# MYO_ESPControlBoard_Rev_1.net
KiCad netlist of a schematic drawn in EAGLE
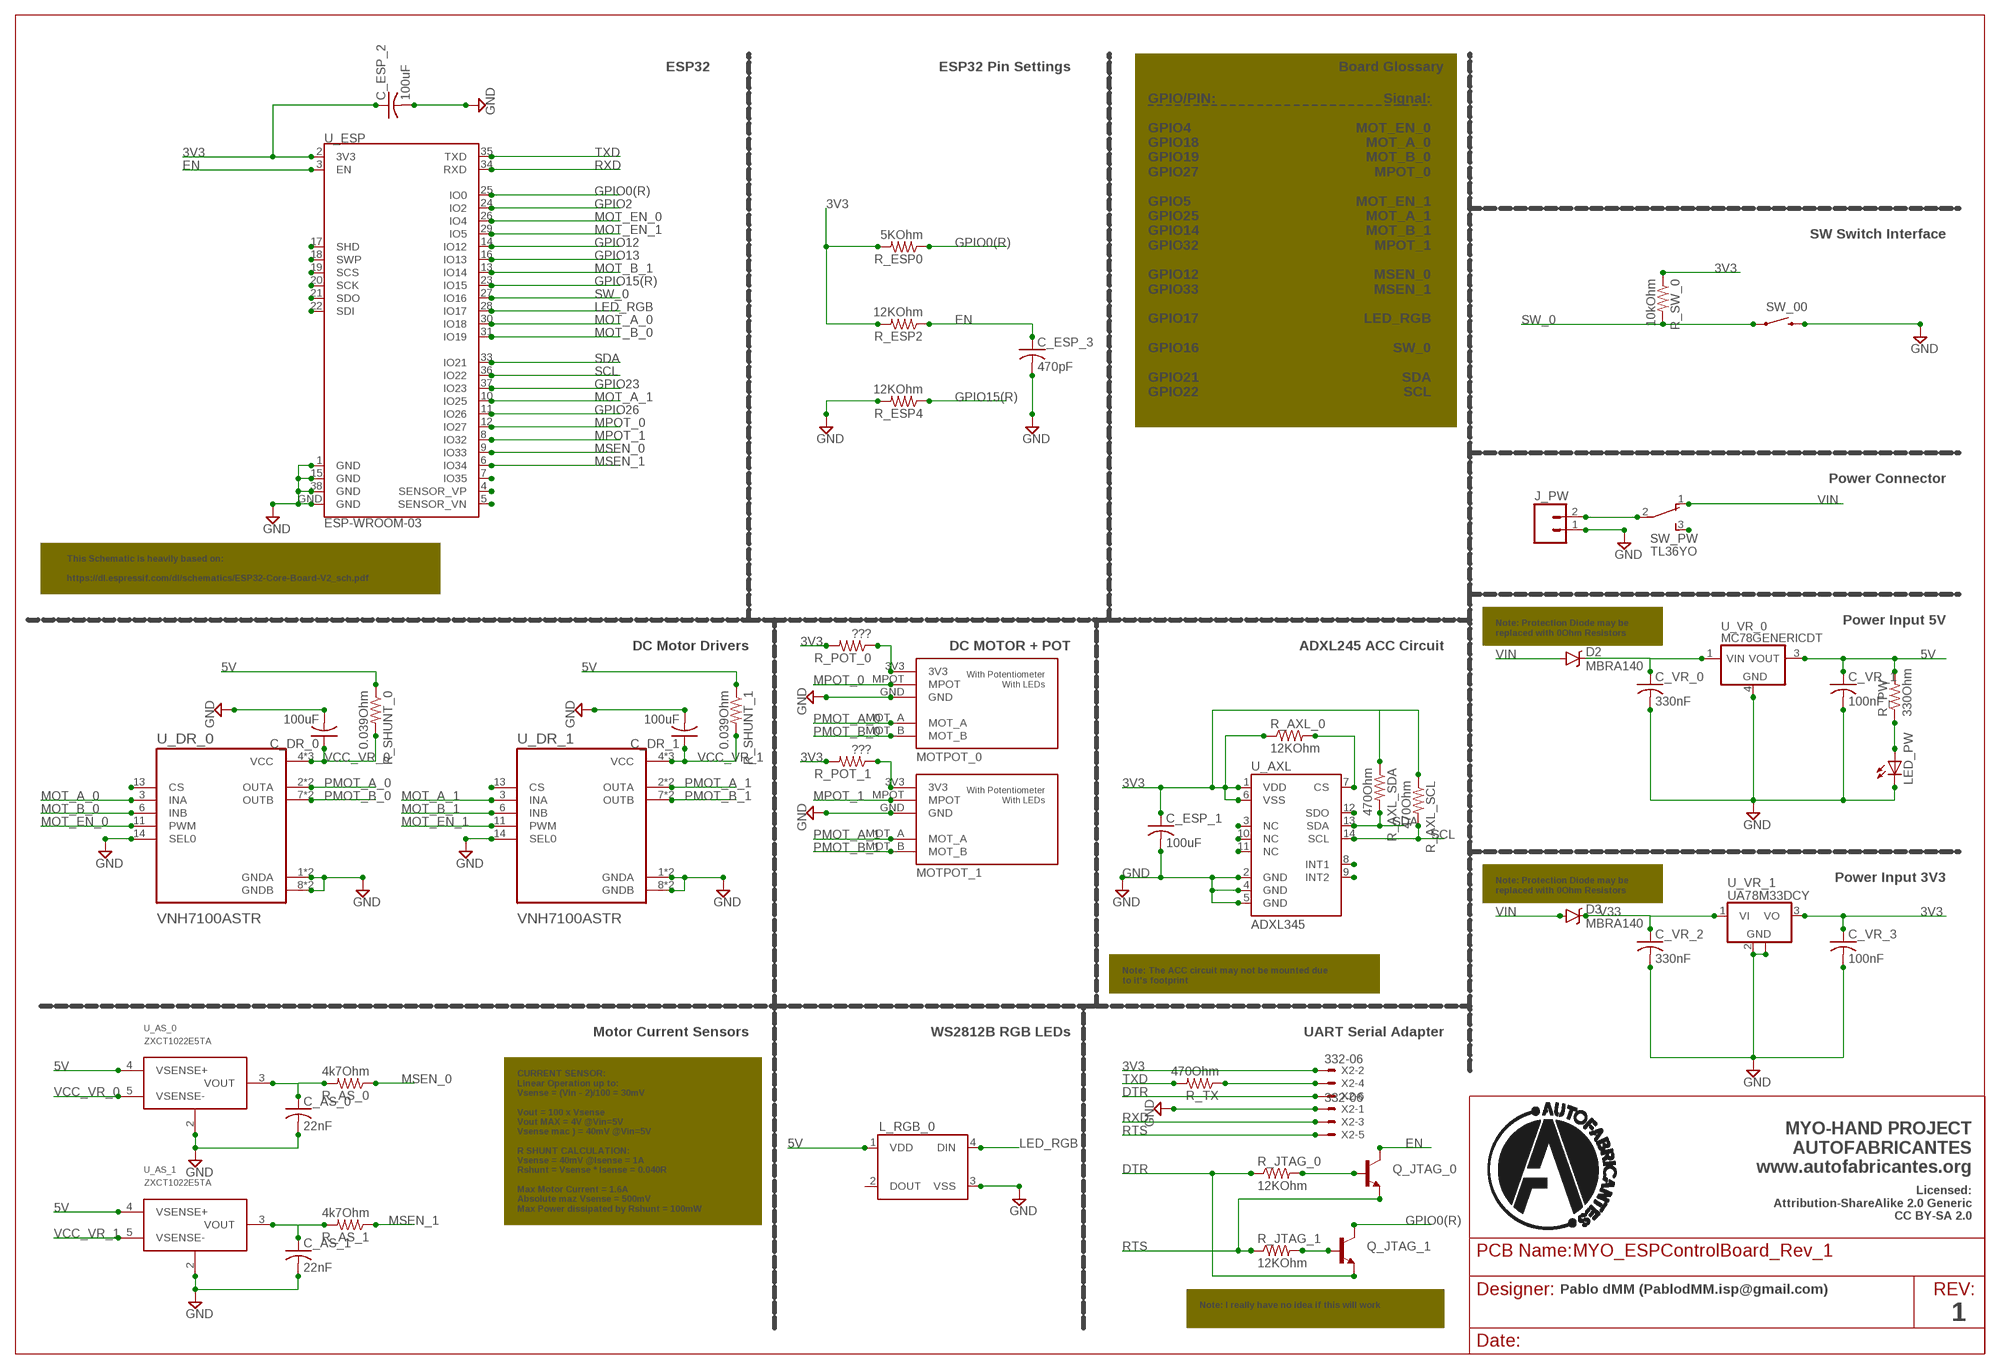
[diagram p0: schematic, sheet 1]

(export (version "E")
  (design (tool "Eeschema 10.0.6"))
  (components
    (comp (ref "C_AS_0")
      (value "22nF")
      (footprint "eagle-import:C0805K")
      (libsource (lib "eagle-import") (part "C-USC0805K"))
    )
    (comp (ref "C_AS_1")
      (value "22nF")
      (footprint "eagle-import:C0805K")
      (libsource (lib "eagle-import") (part "C-USC0805K"))
    )
    (comp (ref "C_DR_0")
      (value "100uF")
      (footprint "eagle-import:C0805K")
      (libsource (lib "eagle-import") (part "C-USC0805K"))
    )
    (comp (ref "C_DR_1")
      (value "100uF")
      (footprint "eagle-import:C0805K")
      (libsource (lib "eagle-import") (part "C-USC0805K"))
    )
    (comp (ref "C_ESP_1")
      (value "100uF")
      (footprint "eagle-import:C0805K")
      (libsource (lib "eagle-import") (part "C-USC0805K"))
    )
    (comp (ref "C_ESP_2")
      (value "100uF")
      (footprint "eagle-import:C0805K")
      (libsource (lib "eagle-import") (part "C-USC0805K"))
    )
    (comp (ref "C_ESP_3")
      (value "470pF")
      (footprint "eagle-import:C0805K")
      (libsource (lib "eagle-import") (part "C-USC0805K"))
    )
    (comp (ref "C_VR_0")
      (value "330nF")
      (footprint "eagle-import:C0805")
      (libsource (lib "eagle-import") (part "C-USC0805"))
    )
    (comp (ref "C_VR_1")
      (value "100nF")
      (footprint "eagle-import:C0805")
      (libsource (lib "eagle-import") (part "C-USC0805"))
    )
    (comp (ref "C_VR_2")
      (value "330nF")
      (footprint "eagle-import:C0805")
      (libsource (lib "eagle-import") (part "C-USC0805"))
    )
    (comp (ref "C_VR_3")
      (value "100nF")
      (footprint "eagle-import:C0805")
      (libsource (lib "eagle-import") (part "C-USC0805"))
    )
    (comp (ref "D2")
      (value "MBRA140")
      (footprint "eagle-import:SMA-DIODE")
      (libsource (lib "eagle-import") (part "MBRA140"))
    )
    (comp (ref "D3")
      (value "MBRA140")
      (footprint "eagle-import:SMA-DIODE")
      (libsource (lib "eagle-import") (part "MBRA140"))
    )
    (comp (ref "J_PW")
      (value "M02-JST-2MM-SMT")
      (footprint "eagle-import:JST-2-SMD")
      (libsource (lib "eagle-import") (part "M02-JST-2MM-SMT"))
    )
    (comp (ref "LED_PW")
      (value "LEDSMT1206")
      (footprint "eagle-import:1206")
      (libsource (lib "eagle-import") (part "LEDSMT1206"))
    )
    (comp (ref "L_RGB_0")
      (value "WS2812B")
      (footprint "eagle-import:WS2812B")
      (libsource (lib "eagle-import") (part "WS2812B"))
    )
    (comp (ref "MOTPOT_0")
      (value "POLOLU_MOT_POT")
      (footprint "eagle-import:POLOLU_MOT_POT")
      (libsource (lib "eagle-import") (part "POLOLU_MOT_POT"))
    )
    (comp (ref "MOTPOT_1")
      (value "POLOLU_MOT_POT")
      (footprint "eagle-import:POLOLU_MOT_POT")
      (libsource (lib "eagle-import") (part "POLOLU_MOT_POT"))
    )
    (comp (ref "Q_JTAG_0")
      (value "TRANSISTOR_NPNSOT23-3")
      (footprint "eagle-import:SOT23-3")
      (libsource (lib "eagle-import") (part "TRANSISTOR_NPNSOT23-3"))
    )
    (comp (ref "Q_JTAG_1")
      (value "TRANSISTOR_NPNSOT23-3")
      (footprint "eagle-import:SOT23-3")
      (libsource (lib "eagle-import") (part "TRANSISTOR_NPNSOT23-3"))
    )
    (comp (ref "R_AS_0")
      (value "4k7Ohm")
      (footprint "eagle-import:M0805")
      (libsource (lib "eagle-import") (part "R-US_M0805"))
    )
    (comp (ref "R_AS_1")
      (value "4k7Ohm")
      (footprint "eagle-import:M0805")
      (libsource (lib "eagle-import") (part "R-US_M0805"))
    )
    (comp (ref "R_AXL_0")
      (value "12KOhm")
      (footprint "eagle-import:M0805")
      (libsource (lib "eagle-import") (part "R-US_M0805"))
    )
    (comp (ref "R_AXL_SCL")
      (value "470Ohm")
      (footprint "eagle-import:M0805")
      (libsource (lib "eagle-import") (part "R-US_M0805"))
    )
    (comp (ref "R_AXL_SDA")
      (value "470Ohm")
      (footprint "eagle-import:M0805")
      (libsource (lib "eagle-import") (part "R-US_M0805"))
    )
    (comp (ref "R_ESP0")
      (value "5KOhm")
      (footprint "eagle-import:M0805")
      (libsource (lib "eagle-import") (part "R-US_M0805"))
    )
    (comp (ref "R_ESP2")
      (value "12KOhm")
      (footprint "eagle-import:M0805")
      (libsource (lib "eagle-import") (part "R-US_M0805"))
    )
    (comp (ref "R_ESP4")
      (value "12KOhm")
      (footprint "eagle-import:M0805")
      (libsource (lib "eagle-import") (part "R-US_M0805"))
    )
    (comp (ref "R_JTAG_0")
      (value "12KOhm")
      (footprint "eagle-import:M0805")
      (libsource (lib "eagle-import") (part "R-US_M0805"))
    )
    (comp (ref "R_JTAG_1")
      (value "12KOhm")
      (footprint "eagle-import:M0805")
      (libsource (lib "eagle-import") (part "R-US_M0805"))
    )
    (comp (ref "R_POT_0")
      (value "???")
      (footprint "eagle-import:M0805")
      (libsource (lib "eagle-import") (part "R-US_M0805"))
    )
    (comp (ref "R_POT_1")
      (value "???")
      (footprint "eagle-import:M0805")
      (libsource (lib "eagle-import") (part "R-US_M0805"))
    )
    (comp (ref "R_PW")
      (value "330Ohm")
      (footprint "eagle-import:M0805")
      (libsource (lib "eagle-import") (part "R-US_M0805"))
    )
    (comp (ref "R_SHUNT_0")
      (value "0.039Ohm")
      (footprint "eagle-import:M0805")
      (libsource (lib "eagle-import") (part "R-US_M0805"))
    )
    (comp (ref "R_SHUNT_1")
      (value "0.039Ohm")
      (footprint "eagle-import:M0805")
      (libsource (lib "eagle-import") (part "R-US_M0805"))
    )
    (comp (ref "R_SW_0")
      (value "10kOhm")
      (footprint "eagle-import:M0805")
      (libsource (lib "eagle-import") (part "R-US_M0805"))
    )
    (comp (ref "R_TX")
      (value "470Ohm")
      (footprint "eagle-import:M0805")
      (libsource (lib "eagle-import") (part "R-US_M0805"))
    )
    (comp (ref "SW_00")
      (value "SWITCH-MOMENTARY-2TACTILE-SWITCH-SMD-RIGHT-ANGLE")
      (footprint "eagle-import:TACTILE_SWITCH-SMD-RIGHT-ANGLE")
      (libsource (lib "eagle-import") (part "SWITCH-MOMENTARY-2TACTILE-SWITCH-SMD-RIGHT-ANGLE"))
    )
    (comp (ref "SW_PW")
      (value "TL36YO")
      (footprint "eagle-import:TL3XYO")
      (libsource (lib "eagle-import") (part "TL36YO"))
    )
    (comp (ref "U_AS_0")
      (value "ZXCT1022E5TA")
      (footprint "eagle-import:SOT95P270X145-5N(SOT23-5)")
      (fields (field (name "DIGI-KEY_PART_NUMBER") "ZXCT1022E5TACT-ND") (field (name "MF") "Diodes Inc."))
      (libsource (lib "eagle-import") (part "ZXCT1022E5TA"))
    )
    (comp (ref "U_AS_1")
      (value "ZXCT1022E5TA")
      (footprint "eagle-import:SOT95P270X145-5N(SOT23-5)")
      (fields (field (name "DIGI-KEY_PART_NUMBER") "ZXCT1022E5TACT-ND") (field (name "MF") "Diodes Inc."))
      (libsource (lib "eagle-import") (part "ZXCT1022E5TA"))
    )
    (comp (ref "U_AXL")
      (value "ADXL345")
      (footprint "eagle-import:LGA14")
      (libsource (lib "eagle-import") (part "ADXL345"))
    )
    (comp (ref "U_DR_0")
      (value "VNH7100ASTR")
      (footprint "eagle-import:SOIC127P600X175-16N")
      (fields (field (name "MF") "STMicroelectronics"))
      (libsource (lib "eagle-import") (part "VNH7100ASTR"))
    )
    (comp (ref "U_DR_1")
      (value "VNH7100ASTR")
      (footprint "eagle-import:SOIC127P600X175-16N")
      (fields (field (name "MF") "STMicroelectronics"))
      (libsource (lib "eagle-import") (part "VNH7100ASTR"))
    )
    (comp (ref "U_ESP")
      (value "ESP-WROOM-03")
      (footprint "eagle-import:ESP-WROOM-03")
      (libsource (lib "eagle-import") (part "ESP-WROOM-03"))
    )
    (comp (ref "U_VR_0")
      (value "MC78GENERICDT")
      (footprint "eagle-import:DPAK-3")
      (libsource (lib "eagle-import") (part "MC78DTGENERIC"))
    )
    (comp (ref "U_VR_1")
      (value "UA78M33DCY")
      (footprint "eagle-import:SOT223")
      (libsource (lib "eagle-import") (part "UA78MDCY33"))
    )
    (comp (ref "X2")
      (value "332-06")
      (footprint "eagle-import:332-06")
      (libsource (lib "eagle-import") (part "332-06"))
    )
  )
  (nets
    (net (code "1") (name "/3V3") (class "Default")
      (node (ref "C_ESP_1") (pin "1") (pinfunction "1_1") (pintype "passive"))
      (node (ref "C_ESP_2") (pin "1") (pinfunction "1_1") (pintype "passive"))
      (node (ref "C_VR_3") (pin "1") (pinfunction "1_1") (pintype "passive"))
      (node (ref "R_AXL_0") (pin "1") (pinfunction "1_1") (pintype "passive"))
      (node (ref "R_AXL_SCL") (pin "1") (pinfunction "1_1") (pintype "passive"))
      (node (ref "R_AXL_SDA") (pin "1") (pinfunction "1_1") (pintype "passive"))
      (node (ref "R_ESP0") (pin "2") (pinfunction "2_2") (pintype "passive"))
      (node (ref "R_ESP2") (pin "2") (pinfunction "2_2") (pintype "passive"))
      (node (ref "R_POT_0") (pin "2") (pinfunction "2_2") (pintype "passive"))
      (node (ref "R_POT_1") (pin "2") (pinfunction "2_2") (pintype "passive"))
      (node (ref "R_SW_0") (pin "1") (pinfunction "1_1") (pintype "passive"))
      (node (ref "U_AXL") (pin "1") (pinfunction "VDD_1") (pintype "bidirectional"))
      (node (ref "U_AXL") (pin "6") (pinfunction "VSS_6") (pintype "bidirectional"))
      (node (ref "U_ESP") (pin "2") (pinfunction "3V3_2") (pintype "bidirectional"))
      (node (ref "U_VR_1") (pin "3") (pinfunction "VO_3") (pintype "passive"))
      (node (ref "X2") (pin "2") (pinfunction "S_2") (pintype "passive"))
    )
    (net (code "2") (name "/5V") (class "Default")
      (node (ref "C_VR_1") (pin "1") (pinfunction "1_1") (pintype "passive"))
      (node (ref "L_RGB_0") (pin "1") (pinfunction "VDD_1") (pintype "power_in"))
      (node (ref "R_PW") (pin "2") (pinfunction "2_2") (pintype "passive"))
      (node (ref "R_SHUNT_0") (pin "1") (pinfunction "1_1") (pintype "passive"))
      (node (ref "R_SHUNT_1") (pin "1") (pinfunction "1_1") (pintype "passive"))
      (node (ref "U_AS_0") (pin "4") (pinfunction "VSENSE+_4") (pintype "input"))
      (node (ref "U_AS_1") (pin "4") (pinfunction "VSENSE+_4") (pintype "input"))
      (node (ref "U_VR_0") (pin "3") (pinfunction "VOUT_3") (pintype "power_in"))
    )
    (net (code "3") (name "/DTR") (class "Default")
      (node (ref "Q_JTAG_1") (pin "2") (pinfunction "E_2") (pintype "passive"))
      (node (ref "R_JTAG_0") (pin "1") (pinfunction "1_1") (pintype "passive"))
      (node (ref "X2") (pin "6") (pinfunction "S_6") (pintype "passive"))
    )
    (net (code "4") (name "/EN") (class "Default")
      (node (ref "C_ESP_3") (pin "1") (pinfunction "1_1") (pintype "passive"))
      (node (ref "Q_JTAG_0") (pin "3") (pinfunction "C_3") (pintype "passive"))
      (node (ref "R_ESP2") (pin "1") (pinfunction "1_1") (pintype "passive"))
      (node (ref "U_ESP") (pin "3") (pinfunction "EN_3") (pintype "bidirectional"))
    )
    (net (code "5") (name "/GPIO0(R)") (class "Default")
      (node (ref "Q_JTAG_1") (pin "3") (pinfunction "C_3") (pintype "passive"))
      (node (ref "R_ESP0") (pin "1") (pinfunction "1_1") (pintype "passive"))
      (node (ref "U_ESP") (pin "25") (pinfunction "IO0_25") (pintype "bidirectional"))
    )
    (net (code "6") (name "/GPIO2") (class "Default")
      (node (ref "U_ESP") (pin "24") (pinfunction "IO2_24") (pintype "bidirectional"))
    )
    (net (code "7") (name "/GPIO12") (class "Default")
      (node (ref "U_ESP") (pin "14") (pinfunction "IO12_14") (pintype "bidirectional"))
    )
    (net (code "8") (name "/GPIO13") (class "Default")
      (node (ref "U_ESP") (pin "16") (pinfunction "IO13_16") (pintype "bidirectional"))
    )
    (net (code "9") (name "/GPIO15(R)") (class "Default")
      (node (ref "R_ESP4") (pin "1") (pinfunction "1_1") (pintype "passive"))
      (node (ref "U_ESP") (pin "23") (pinfunction "IO15_23") (pintype "bidirectional"))
    )
    (net (code "10") (name "/GPIO23") (class "Default")
      (node (ref "U_ESP") (pin "37") (pinfunction "IO23_37") (pintype "bidirectional"))
    )
    (net (code "11") (name "/GPIO26") (class "Default")
      (node (ref "U_ESP") (pin "11") (pinfunction "IO26_11") (pintype "bidirectional"))
    )
    (net (code "12") (name "/LED_RGB") (class "Default")
      (node (ref "L_RGB_0") (pin "4") (pinfunction "DIN_4") (pintype "input"))
      (node (ref "U_ESP") (pin "28") (pinfunction "IO17_28") (pintype "bidirectional"))
    )
    (net (code "13") (name "/MOT_A_0") (class "Default")
      (node (ref "U_DR_0") (pin "3") (pinfunction "INA_3") (pintype "input"))
      (node (ref "U_ESP") (pin "30") (pinfunction "IO18_30") (pintype "bidirectional"))
    )
    (net (code "14") (name "/MOT_A_1") (class "Default")
      (node (ref "U_DR_1") (pin "3") (pinfunction "INA_3") (pintype "input"))
      (node (ref "U_ESP") (pin "10") (pinfunction "IO25_10") (pintype "bidirectional"))
    )
    (net (code "15") (name "/MOT_B_0") (class "Default")
      (node (ref "U_DR_0") (pin "6") (pinfunction "INB_6") (pintype "input"))
      (node (ref "U_ESP") (pin "31") (pinfunction "IO19_31") (pintype "bidirectional"))
    )
    (net (code "16") (name "/MOT_B_1") (class "Default")
      (node (ref "U_DR_1") (pin "6") (pinfunction "INB_6") (pintype "input"))
      (node (ref "U_ESP") (pin "13") (pinfunction "IO14_13") (pintype "bidirectional"))
    )
    (net (code "17") (name "/MOT_EN_0") (class "Default")
      (node (ref "U_DR_0") (pin "11") (pinfunction "PWM_11") (pintype "input"))
      (node (ref "U_ESP") (pin "26") (pinfunction "IO4_26") (pintype "bidirectional"))
    )
    (net (code "18") (name "/MOT_EN_1") (class "Default")
      (node (ref "U_DR_1") (pin "11") (pinfunction "PWM_11") (pintype "input"))
      (node (ref "U_ESP") (pin "29") (pinfunction "IO5_29") (pintype "bidirectional"))
    )
    (net (code "19") (name "/MPOT_0") (class "Default")
      (node (ref "MOTPOT_0") (pin "MPOT") (pinfunction "MPOT_MPOT") (pintype "bidirectional"))
      (node (ref "U_ESP") (pin "12") (pinfunction "IO27_12") (pintype "bidirectional"))
    )
    (net (code "20") (name "/MPOT_1") (class "Default")
      (node (ref "MOTPOT_1") (pin "MPOT") (pinfunction "MPOT_MPOT") (pintype "bidirectional"))
      (node (ref "U_ESP") (pin "8") (pinfunction "IO32_8") (pintype "bidirectional"))
    )
    (net (code "21") (name "/MSEN_0") (class "Default")
      (node (ref "R_AS_0") (pin "1") (pinfunction "1_1") (pintype "passive"))
      (node (ref "U_ESP") (pin "9") (pinfunction "IO33_9") (pintype "bidirectional"))
    )
    (net (code "22") (name "/MSEN_1") (class "Default")
      (node (ref "R_AS_1") (pin "1") (pinfunction "1_1") (pintype "passive"))
      (node (ref "U_ESP") (pin "6") (pinfunction "IO34_6") (pintype "bidirectional"))
    )
    (net (code "23") (name "/PMOT_A_0") (class "Default")
      (node (ref "MOTPOT_0") (pin "MOT_A") (pinfunction "MOT_A_MOT_A") (pintype "bidirectional"))
      (node (ref "U_DR_0") (pin "15") (pinfunction "OUTA_15") (pintype "output"))
      (node (ref "U_DR_0") (pin "2") (pinfunction "OUTA_2") (pintype "output"))
    )
    (net (code "24") (name "/PMOT_A_1") (class "Default")
      (node (ref "MOTPOT_1") (pin "MOT_A") (pinfunction "MOT_A_MOT_A") (pintype "bidirectional"))
      (node (ref "U_DR_1") (pin "15") (pinfunction "OUTA_15") (pintype "output"))
      (node (ref "U_DR_1") (pin "2") (pinfunction "OUTA_2") (pintype "output"))
    )
    (net (code "25") (name "/PMOT_B_0") (class "Default")
      (node (ref "MOTPOT_0") (pin "MOT_B") (pinfunction "MOT_B_MOT_B") (pintype "bidirectional"))
      (node (ref "U_DR_0") (pin "10") (pinfunction "OUTB_10") (pintype "output"))
      (node (ref "U_DR_0") (pin "7") (pinfunction "OUTB_7") (pintype "output"))
    )
    (net (code "26") (name "/PMOT_B_1") (class "Default")
      (node (ref "MOTPOT_1") (pin "MOT_B") (pinfunction "MOT_B_MOT_B") (pintype "bidirectional"))
      (node (ref "U_DR_1") (pin "10") (pinfunction "OUTB_10") (pintype "output"))
      (node (ref "U_DR_1") (pin "7") (pinfunction "OUTB_7") (pintype "output"))
    )
    (net (code "27") (name "/RTS") (class "Default")
      (node (ref "Q_JTAG_0") (pin "2") (pinfunction "E_2") (pintype "passive"))
      (node (ref "R_JTAG_1") (pin "1") (pinfunction "1_1") (pintype "passive"))
      (node (ref "X2") (pin "5") (pinfunction "S_5") (pintype "passive"))
    )
    (net (code "28") (name "/RXD") (class "Default")
      (node (ref "U_ESP") (pin "34") (pinfunction "RXD_34") (pintype "bidirectional"))
      (node (ref "X2") (pin "3") (pinfunction "S_3") (pintype "passive"))
    )
    (net (code "29") (name "/SCL") (class "Default")
      (node (ref "R_AXL_SCL") (pin "2") (pinfunction "2_2") (pintype "passive"))
      (node (ref "U_AXL") (pin "14") (pinfunction "SCL_14") (pintype "bidirectional"))
      (node (ref "U_ESP") (pin "36") (pinfunction "IO22_36") (pintype "bidirectional"))
    )
    (net (code "30") (name "/SDA") (class "Default")
      (node (ref "R_AXL_SDA") (pin "2") (pinfunction "2_2") (pintype "passive"))
      (node (ref "U_AXL") (pin "13") (pinfunction "SDA_13") (pintype "bidirectional"))
      (node (ref "U_ESP") (pin "33") (pinfunction "IO21_33") (pintype "bidirectional"))
    )
    (net (code "31") (name "/SW_0") (class "Default")
      (node (ref "R_SW_0") (pin "2") (pinfunction "2_2") (pintype "passive"))
      (node (ref "SW_00") (pin "1") (pinfunction "1_1") (pintype "passive"))
      (node (ref "U_ESP") (pin "27") (pinfunction "IO16_27") (pintype "bidirectional"))
    )
    (net (code "32") (name "/TXD") (class "Default")
      (node (ref "R_TX") (pin "2") (pinfunction "2_2") (pintype "passive"))
      (node (ref "U_ESP") (pin "35") (pinfunction "TXD_35") (pintype "bidirectional"))
    )
    (net (code "33") (name "/V33") (class "Default")
      (node (ref "C_VR_2") (pin "1") (pinfunction "1_1") (pintype "passive"))
      (node (ref "D3") (pin "C") (pinfunction "C_C") (pintype "passive"))
      (node (ref "U_VR_1") (pin "1") (pinfunction "VI_1") (pintype "input"))
    )
    (net (code "34") (name "/VCC_VR_0") (class "Default")
      (node (ref "C_DR_0") (pin "1") (pinfunction "1_1") (pintype "passive"))
      (node (ref "R_SHUNT_0") (pin "2") (pinfunction "2_2") (pintype "passive"))
      (node (ref "U_AS_0") (pin "5") (pinfunction "VSENSE-_5") (pintype "input"))
      (node (ref "U_DR_0") (pin "12") (pinfunction "VCC_12") (pintype "power_in"))
      (node (ref "U_DR_0") (pin "4") (pinfunction "VCC_4") (pintype "power_in"))
      (node (ref "U_DR_0") (pin "5") (pinfunction "VCC_5") (pintype "power_in"))
    )
    (net (code "35") (name "/VCC_VR_1") (class "Default")
      (node (ref "C_DR_1") (pin "1") (pinfunction "1_1") (pintype "passive"))
      (node (ref "R_SHUNT_1") (pin "2") (pinfunction "2_2") (pintype "passive"))
      (node (ref "U_AS_1") (pin "5") (pinfunction "VSENSE-_5") (pintype "input"))
      (node (ref "U_DR_1") (pin "12") (pinfunction "VCC_12") (pintype "power_in"))
      (node (ref "U_DR_1") (pin "4") (pinfunction "VCC_4") (pintype "power_in"))
      (node (ref "U_DR_1") (pin "5") (pinfunction "VCC_5") (pintype "power_in"))
    )
    (net (code "36") (name "/VIN") (class "Default")
      (node (ref "D2") (pin "A") (pinfunction "A_A") (pintype "passive"))
      (node (ref "D3") (pin "A") (pinfunction "A_A") (pintype "passive"))
      (node (ref "SW_PW") (pin "1") (pinfunction "O_1") (pintype "passive"))
    )
    (net (code "37") (name "GND") (class "Default")
      (node (ref "C_AS_0") (pin "2") (pinfunction "2_2") (pintype "passive"))
      (node (ref "C_AS_1") (pin "2") (pinfunction "2_2") (pintype "passive"))
      (node (ref "C_DR_0") (pin "2") (pinfunction "2_2") (pintype "passive"))
      (node (ref "C_DR_1") (pin "2") (pinfunction "2_2") (pintype "passive"))
      (node (ref "C_ESP_1") (pin "2") (pinfunction "2_2") (pintype "passive"))
      (node (ref "C_ESP_2") (pin "2") (pinfunction "2_2") (pintype "passive"))
      (node (ref "C_ESP_3") (pin "2") (pinfunction "2_2") (pintype "passive"))
      (node (ref "C_VR_0") (pin "2") (pinfunction "2_2") (pintype "passive"))
      (node (ref "C_VR_1") (pin "2") (pinfunction "2_2") (pintype "passive"))
      (node (ref "C_VR_2") (pin "2") (pinfunction "2_2") (pintype "passive"))
      (node (ref "C_VR_3") (pin "2") (pinfunction "2_2") (pintype "passive"))
      (node (ref "J_PW") (pin "1") (pinfunction "1_1") (pintype "passive"))
      (node (ref "LED_PW") (pin "C") (pinfunction "C_C") (pintype "passive"))
      (node (ref "L_RGB_0") (pin "3") (pinfunction "VSS_3") (pintype "power_in"))
      (node (ref "MOTPOT_0") (pin "GND") (pinfunction "GND_GND") (pintype "bidirectional"))
      (node (ref "MOTPOT_1") (pin "GND") (pinfunction "GND_GND") (pintype "bidirectional"))
      (node (ref "R_ESP4") (pin "2") (pinfunction "2_2") (pintype "passive"))
      (node (ref "SW_00") (pin "2") (pinfunction "2_2") (pintype "passive"))
      (node (ref "U_AS_0") (pin "2") (pinfunction "GND_2") (pintype "passive"))
      (node (ref "U_AS_1") (pin "2") (pinfunction "GND_2") (pintype "passive"))
      (node (ref "U_AXL") (pin "2") (pinfunction "GND_2") (pintype "bidirectional"))
      (node (ref "U_AXL") (pin "4") (pinfunction "GND_4") (pintype "bidirectional"))
      (node (ref "U_AXL") (pin "5") (pinfunction "GND_5") (pintype "bidirectional"))
      (node (ref "U_DR_0") (pin "1") (pinfunction "GNDA_1") (pintype "power_in"))
      (node (ref "U_DR_0") (pin "14") (pinfunction "SEL0_14") (pintype "input"))
      (node (ref "U_DR_0") (pin "16") (pinfunction "GNDA_16") (pintype "power_in"))
      (node (ref "U_DR_0") (pin "8") (pinfunction "GNDB_8") (pintype "power_in"))
      (node (ref "U_DR_0") (pin "9") (pinfunction "GNDB_9") (pintype "power_in"))
      (node (ref "U_DR_1") (pin "1") (pinfunction "GNDA_1") (pintype "power_in"))
      (node (ref "U_DR_1") (pin "14") (pinfunction "SEL0_14") (pintype "input"))
      (node (ref "U_DR_1") (pin "16") (pinfunction "GNDA_16") (pintype "power_in"))
      (node (ref "U_DR_1") (pin "8") (pinfunction "GNDB_8") (pintype "power_in"))
      (node (ref "U_DR_1") (pin "9") (pinfunction "GNDB_9") (pintype "power_in"))
      (node (ref "U_ESP") (pin "1") (pinfunction "GND_1") (pintype "bidirectional"))
      (node (ref "U_ESP") (pin "15") (pinfunction "GND_15") (pintype "bidirectional"))
      (node (ref "U_ESP") (pin "38") (pinfunction "GND_38") (pintype "bidirectional"))
      (node (ref "U_ESP") (pin "GND") (pinfunction "GND_GND") (pintype "bidirectional"))
      (node (ref "U_VR_0") (pin "4") (pinfunction "GND_4") (pintype "power_in"))
      (node (ref "U_VR_1") (pin "2") (pinfunction "GND_2") (pintype "passive"))
      (node (ref "U_VR_1") (pin "4") (pinfunction "GND_4") (pintype "passive"))
      (node (ref "X2") (pin "1") (pinfunction "S_1") (pintype "passive"))
    )
    (net (code "38") (name "Net-(LED_PW-PadA)") (class "Default")
      (node (ref "LED_PW") (pin "A") (pinfunction "A_A") (pintype "passive"))
      (node (ref "R_PW") (pin "1") (pinfunction "1_1") (pintype "passive"))
    )
    (net (code "39") (name "Net-(MOTPOT_0-Pad3V3)") (class "Default")
      (node (ref "MOTPOT_0") (pin "3V3") (pinfunction "3V3_3V3") (pintype "bidirectional"))
      (node (ref "R_POT_0") (pin "1") (pinfunction "1_1") (pintype "passive"))
    )
    (net (code "40") (name "Net-(MOTPOT_1-Pad3V3)") (class "Default")
      (node (ref "MOTPOT_1") (pin "3V3") (pinfunction "3V3_3V3") (pintype "bidirectional"))
      (node (ref "R_POT_1") (pin "1") (pinfunction "1_1") (pintype "passive"))
    )
    (net (code "41") (name "Net-(Q_JTAG_0-B)") (class "Default")
      (node (ref "Q_JTAG_0") (pin "1") (pinfunction "B_1") (pintype "passive"))
      (node (ref "R_JTAG_0") (pin "2") (pinfunction "2_2") (pintype "passive"))
    )
    (net (code "42") (name "Net-(Q_JTAG_1-B)") (class "Default")
      (node (ref "Q_JTAG_1") (pin "1") (pinfunction "B_1") (pintype "passive"))
      (node (ref "R_JTAG_1") (pin "2") (pinfunction "2_2") (pintype "passive"))
    )
    (net (code "43") (name "Net-(SW_PW-P)") (class "Default")
      (node (ref "J_PW") (pin "2") (pinfunction "2_2") (pintype "passive"))
      (node (ref "SW_PW") (pin "2") (pinfunction "P_2") (pintype "passive"))
    )
    (net (code "44") (name "Net-(U_AS_0-VOUT)") (class "Default")
      (node (ref "C_AS_0") (pin "1") (pinfunction "1_1") (pintype "passive"))
      (node (ref "R_AS_0") (pin "2") (pinfunction "2_2") (pintype "passive"))
      (node (ref "U_AS_0") (pin "3") (pinfunction "VOUT_3") (pintype "output"))
    )
    (net (code "45") (name "Net-(U_AS_1-VOUT)") (class "Default")
      (node (ref "C_AS_1") (pin "1") (pinfunction "1_1") (pintype "passive"))
      (node (ref "R_AS_1") (pin "2") (pinfunction "2_2") (pintype "passive"))
      (node (ref "U_AS_1") (pin "3") (pinfunction "VOUT_3") (pintype "output"))
    )
    (net (code "46") (name "Net-(U_AXL-CS)") (class "Default")
      (node (ref "R_AXL_0") (pin "2") (pinfunction "2_2") (pintype "passive"))
      (node (ref "U_AXL") (pin "7") (pinfunction "CS_7") (pintype "bidirectional"))
    )
    (net (code "47") (name "Net-(U_VR_0-VIN)") (class "Default")
      (node (ref "C_VR_0") (pin "1") (pinfunction "1_1") (pintype "passive"))
      (node (ref "D2") (pin "C") (pinfunction "C_C") (pintype "passive"))
      (node (ref "U_VR_0") (pin "1") (pinfunction "VIN_1") (pintype "power_in"))
    )
    (net (code "48") (name "Net-(X2D-S)") (class "Default")
      (node (ref "R_TX") (pin "1") (pinfunction "1_1") (pintype "passive"))
      (node (ref "X2") (pin "4") (pinfunction "S_4") (pintype "passive"))
    )
    (net (code "49") (name "unconnected-(L_RGB_0-DOUT-Pad2)") (class "Default")
      (node (ref "L_RGB_0") (pin "2") (pinfunction "DOUT_2") (pintype "output"))
    )
    (net (code "50") (name "unconnected-(SW_PW-S-Pad3)") (class "Default")
      (node (ref "SW_PW") (pin "3") (pinfunction "S_3") (pintype "passive"))
    )
    (net (code "51") (name "unconnected-(U_AXL-INT1-Pad8)") (class "Default")
      (node (ref "U_AXL") (pin "8") (pinfunction "INT1_8") (pintype "bidirectional"))
    )
    (net (code "52") (name "unconnected-(U_AXL-INT2-Pad9)") (class "Default")
      (node (ref "U_AXL") (pin "9") (pinfunction "INT2_9") (pintype "bidirectional"))
    )
    (net (code "53") (name "unconnected-(U_AXL-NC-Pad3)") (class "Default")
      (node (ref "U_AXL") (pin "3") (pinfunction "NC_3") (pintype "bidirectional"))
    )
    (net (code "54") (name "unconnected-(U_AXL-NC-Pad10)") (class "Default")
      (node (ref "U_AXL") (pin "10") (pinfunction "NC_10") (pintype "bidirectional"))
    )
    (net (code "55") (name "unconnected-(U_AXL-NC-Pad11)") (class "Default")
      (node (ref "U_AXL") (pin "11") (pinfunction "NC_11") (pintype "bidirectional"))
    )
    (net (code "56") (name "unconnected-(U_AXL-SDO-Pad12)") (class "Default")
      (node (ref "U_AXL") (pin "12") (pinfunction "SDO_12") (pintype "bidirectional"))
    )
    (net (code "57") (name "unconnected-(U_DR_0-CS-Pad13)") (class "Default")
      (node (ref "U_DR_0") (pin "13") (pinfunction "CS_13") (pintype "input"))
    )
    (net (code "58") (name "unconnected-(U_DR_1-CS-Pad13)") (class "Default")
      (node (ref "U_DR_1") (pin "13") (pinfunction "CS_13") (pintype "input"))
    )
    (net (code "59") (name "unconnected-(U_ESP-IO35-Pad7)") (class "Default")
      (node (ref "U_ESP") (pin "7") (pinfunction "IO35_7") (pintype "bidirectional"))
    )
    (net (code "60") (name "unconnected-(U_ESP-SCK-Pad20)") (class "Default")
      (node (ref "U_ESP") (pin "20") (pinfunction "SCK_20") (pintype "bidirectional"))
    )
    (net (code "61") (name "unconnected-(U_ESP-SCS-Pad19)") (class "Default")
      (node (ref "U_ESP") (pin "19") (pinfunction "SCS_19") (pintype "bidirectional"))
    )
    (net (code "62") (name "unconnected-(U_ESP-SDI-Pad22)") (class "Default")
      (node (ref "U_ESP") (pin "22") (pinfunction "SDI_22") (pintype "bidirectional"))
    )
    (net (code "63") (name "unconnected-(U_ESP-SDO-Pad21)") (class "Default")
      (node (ref "U_ESP") (pin "21") (pinfunction "SDO_21") (pintype "bidirectional"))
    )
    (net (code "64") (name "unconnected-(U_ESP-SENSOR_VN-Pad5)") (class "Default")
      (node (ref "U_ESP") (pin "5") (pinfunction "SENSOR_VN_5") (pintype "bidirectional"))
    )
    (net (code "65") (name "unconnected-(U_ESP-SENSOR_VP-Pad4)") (class "Default")
      (node (ref "U_ESP") (pin "4") (pinfunction "SENSOR_VP_4") (pintype "bidirectional"))
    )
    (net (code "66") (name "unconnected-(U_ESP-SHD-Pad17)") (class "Default")
      (node (ref "U_ESP") (pin "17") (pinfunction "SHD_17") (pintype "bidirectional"))
    )
    (net (code "67") (name "unconnected-(U_ESP-SWP-Pad18)") (class "Default")
      (node (ref "U_ESP") (pin "18") (pinfunction "SWP_18") (pintype "bidirectional"))
    )
  )
)
